# Driver2_TI.net
KiCad netlist of a schematic drawn in Altium Designer
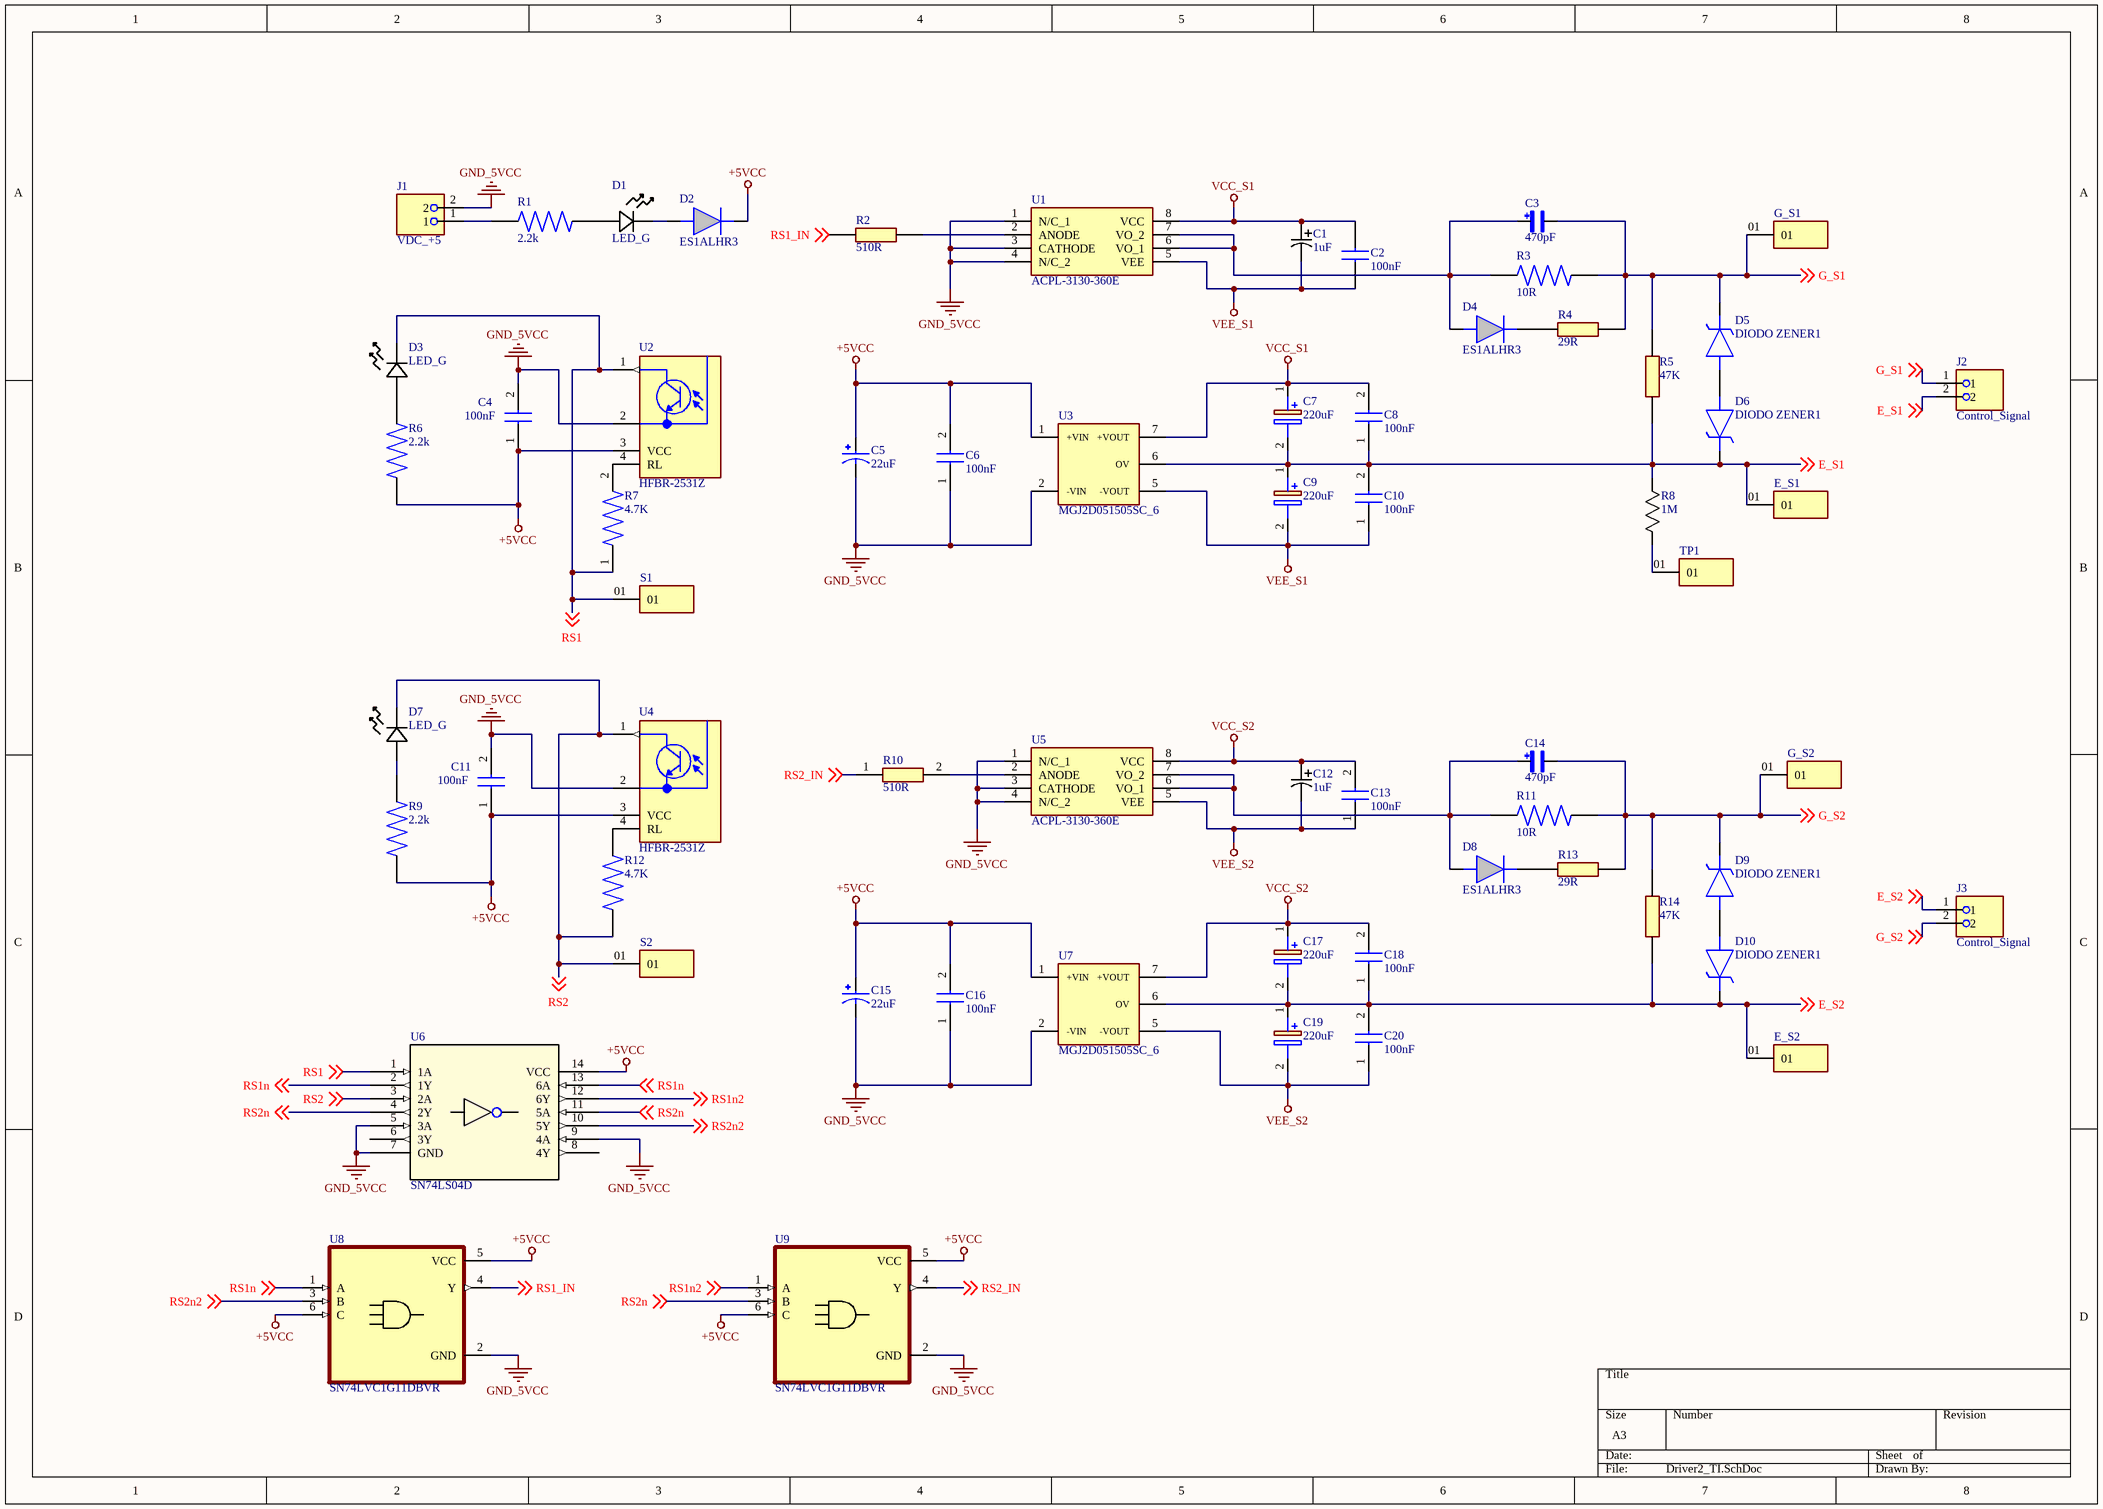
[diagram p0: Driver2_TI.SchDoc]

(export (version "E")
  (design (tool "Eeschema 10.0.6"))
  (components
    (comp (ref "C1")
      (value "1uF")
      (footprint "CAPAE430X550N")
      (description "Capacitor 1uF")
      (libsource (lib "Componentes") (part "UWX1H010MCL1GB"))
    )
    (comp (ref "C2")
      (value "100nF")
      (footprint "SamacSys:CAPC3216X94N")
      (description "Capacitor")
      (fields
        (field (name "MANUFACTURER_PART_NUMBER") "12063C104MAT2A")
        (field (name "MOUSER PART NUMBER") "581-12063C104MAT2A")
      )
      (libsource (lib "") (part "12063C104MAT2A_1"))
    )
    (comp (ref "C3")
      (value "470pF")
      (footprint "CAPC3216X94N")
      (description "Cap Ceramic 470pF 100V C0G 5% Pad SMD 1206 125Â°C T/R")
      (fields (field (name "MF") "KYOCERA AVX Components") (field (name "MP") "12061A471JAT2A"))
      (libsource (lib "Componentes") (part "MC1206N471J101CT"))
    )
    (comp (ref "C4")
      (value "100nF")
      (footprint "SamacSys:CAPC3216X94N")
      (description "Capacitor")
      (fields
        (field (name "MANUFACTURER_PART_NUMBER") "12063C104MAT2A")
        (field (name "MOUSER PART NUMBER") "581-12063C104MAT2A")
      )
      (libsource (lib "*") (part "12063C104MAT2A"))
    )
    (comp (ref "C5")
      (value "22uF")
      (footprint "CAP_EEE1HA220WP")
      (description "22ÂµF 50V Aluminum Electrolytic Capacitors Radial, Can - SMD 1000 Hrs @ 85Â°C")
      (fields (field (name "MF") "Panasonic") (field (name "MP") "EEE1HA220WP"))
      (libsource (lib "Componentes") (part "EEE1HA220WP"))
    )
    (comp (ref "C6")
      (value "100nF")
      (footprint "SamacSys:CAPC3216X94N")
      (description "Capacitor")
      (fields
        (field (name "MANUFACTURER_PART_NUMBER") "12063C104MAT2A")
        (field (name "MOUSER PART NUMBER") "581-12063C104MAT2A")
      )
      (libsource (lib "*") (part "12063C104MAT2A"))
    )
    (comp (ref "C7")
      (value "220uF")
      (footprint "SamacSys:CAPAE1050X1430N")
      (description "Capacitor Polarised")
      (fields
        (field (name "MANUFACTURER_PART_NUMBER") "MAL215097102E3")
        (field (name "MOUSER PART NUMBER") "594-MAL215097102E3")
      )
      (libsource (lib "*") (part "MAL215097102E3"))
    )
    (comp (ref "C8")
      (value "100nF")
      (footprint "SamacSys:CAPC3216X94N")
      (description "Capacitor")
      (fields
        (field (name "MANUFACTURER_PART_NUMBER") "12063C104MAT2A")
        (field (name "MOUSER PART NUMBER") "581-12063C104MAT2A")
      )
      (libsource (lib "*") (part "12063C104MAT2A"))
    )
    (comp (ref "C9")
      (value "220uF")
      (footprint "SamacSys:CAPAE1050X1430N")
      (description "Capacitor Polarised")
      (fields
        (field (name "MANUFACTURER_PART_NUMBER") "MAL215097102E3")
        (field (name "MOUSER PART NUMBER") "594-MAL215097102E3")
      )
      (libsource (lib "*") (part "MAL215097102E3"))
    )
    (comp (ref "C10")
      (value "100nF")
      (footprint "SamacSys:CAPC3216X94N")
      (description "Capacitor")
      (fields
        (field (name "MANUFACTURER_PART_NUMBER") "12063C104MAT2A")
        (field (name "MOUSER PART NUMBER") "581-12063C104MAT2A")
      )
      (libsource (lib "*") (part "12063C104MAT2A"))
    )
    (comp (ref "C11")
      (value "100nF")
      (footprint "SamacSys:CAPC3216X94N")
      (description "Capacitor")
      (fields
        (field (name "MANUFACTURER_PART_NUMBER") "12063C104MAT2A")
        (field (name "MOUSER PART NUMBER") "581-12063C104MAT2A")
      )
      (libsource (lib "*") (part "12063C104MAT2A"))
    )
    (comp (ref "C12")
      (value "1uF")
      (footprint "CAPAE430X550N")
      (description "Capacitor 1uF")
      (libsource (lib "Componentes") (part "UWX1H010MCL1GB"))
    )
    (comp (ref "C13")
      (value "100nF")
      (footprint "SamacSys:CAPC3216X94N")
      (description "Capacitor")
      (fields
        (field (name "MANUFACTURER_PART_NUMBER") "12063C104MAT2A")
        (field (name "MOUSER PART NUMBER") "581-12063C104MAT2A")
      )
      (libsource (lib "*") (part "12063C104MAT2A"))
    )
    (comp (ref "C14")
      (value "470pF")
      (footprint "CAPC3216X94N")
      (description "Cap Ceramic 470pF 100V C0G 5% Pad SMD 1206 125Â°C T/R")
      (fields (field (name "MF") "KYOCERA AVX Components") (field (name "MP") "12061A471JAT2A"))
      (libsource (lib "Componentes") (part "MC1206N471J101CT"))
    )
    (comp (ref "C15")
      (value "22uF")
      (footprint "CAP_EEE1HA220WP")
      (description "22ÂµF 50V Aluminum Electrolytic Capacitors Radial, Can - SMD 1000 Hrs @ 85Â°C")
      (fields (field (name "MF") "Panasonic") (field (name "MP") "EEE1HA220WP"))
      (libsource (lib "Componentes") (part "EEE1HA220WP"))
    )
    (comp (ref "C16")
      (value "100nF")
      (footprint "SamacSys:CAPC3216X94N")
      (description "Capacitor")
      (fields
        (field (name "MANUFACTURER_PART_NUMBER") "12063C104MAT2A")
        (field (name "MOUSER PART NUMBER") "581-12063C104MAT2A")
      )
      (libsource (lib "*") (part "12063C104MAT2A"))
    )
    (comp (ref "C17")
      (value "220uF")
      (footprint "SamacSys:CAPAE1050X1430N")
      (description "Capacitor Polarised")
      (fields
        (field (name "MANUFACTURER_PART_NUMBER") "MAL215097102E3")
        (field (name "MOUSER PART NUMBER") "594-MAL215097102E3")
      )
      (libsource (lib "*") (part "MAL215097102E3"))
    )
    (comp (ref "C18")
      (value "100nF")
      (footprint "SamacSys:CAPC3216X94N")
      (description "Capacitor")
      (fields
        (field (name "MANUFACTURER_PART_NUMBER") "12063C104MAT2A")
        (field (name "MOUSER PART NUMBER") "581-12063C104MAT2A")
      )
      (libsource (lib "*") (part "12063C104MAT2A"))
    )
    (comp (ref "C19")
      (value "220uF")
      (footprint "SamacSys:CAPAE1050X1430N")
      (description "Capacitor Polarised")
      (fields
        (field (name "MANUFACTURER_PART_NUMBER") "MAL215097102E3")
        (field (name "MOUSER PART NUMBER") "594-MAL215097102E3")
      )
      (libsource (lib "*") (part "MAL215097102E3"))
    )
    (comp (ref "C20")
      (value "100nF")
      (footprint "SamacSys:CAPC3216X94N")
      (description "Capacitor")
      (fields
        (field (name "MANUFACTURER_PART_NUMBER") "12063C104MAT2A")
        (field (name "MOUSER PART NUMBER") "581-12063C104MAT2A")
      )
      (libsource (lib "*") (part "12063C104MAT2A"))
    )
    (comp (ref "D1")
      (value "LED_G")
      (footprint "LED_KP-2012_KNB")
      (description "KP-2012SGC")
      (fields (field (name "COPYRIGHT") "Copyright (C) 2025 Ultra Librarian. All rights reserved."))
      (libsource (lib "Componentes") (part "KP-2012SGC"))
    )
    (comp (ref "D2")
      (value "ES1ALHR3")
      (footprint "DIOM4427X25M")
      (description "Rectifiers 1A, 50V, SUPER FAST SM RECTIFIER")
      (fields (field (name "MOUSER PART NUMBER") "821-ES1ALHR3"))
      (libsource (lib "Componentes") (part "ES1ALHR3_1"))
    )
    (comp (ref "D3")
      (value "LED_G")
      (footprint "LED_KP-2012_KNB")
      (description "KP-2012SGC")
      (fields (field (name "COPYRIGHT") "Copyright (C) 2025 Ultra Librarian. All rights reserved."))
      (libsource (lib "Componentes") (part "KP-2012SGC"))
    )
    (comp (ref "D4")
      (value "ES1ALHR3")
      (footprint "DIOM4427X25M")
      (description "Rectifiers 1A, 50V, SUPER FAST SM RECTIFIER")
      (fields (field (name "MOUSER PART NUMBER") "821-ES1ALHR3"))
      (libsource (lib "Componentes") (part "ES1ALHR3_1"))
    )
    (comp (ref "D5")
      (value "DIODO ZENER1")
      (footprint "SamacSys:DIOM5436X247N")
      (description "Zener Diode")
      (fields
        (field (name "MANUFACTURER_PART_NUMBER") "1SMB5931BT3G")
        (field (name "MOUSER PART NUMBER") "863-1SMB5931BT3G")
      )
      (libsource (lib "*") (part "1SMB5931BT3G"))
    )
    (comp (ref "D6")
      (value "DIODO ZENER1")
      (footprint "SamacSys:DIOM5436X247N")
      (description "Zener Diode")
      (fields
        (field (name "MANUFACTURER_PART_NUMBER") "1SMB5931BT3G")
        (field (name "MOUSER PART NUMBER") "863-1SMB5931BT3G")
      )
      (libsource (lib "*") (part "1SMB5931BT3G"))
    )
    (comp (ref "D7")
      (value "LED_G")
      (footprint "LED_KP-2012_KNB")
      (description "KP-2012SGC")
      (fields (field (name "COPYRIGHT") "Copyright (C) 2025 Ultra Librarian. All rights reserved."))
      (libsource (lib "Componentes") (part "KP-2012SGC"))
    )
    (comp (ref "D8")
      (value "ES1ALHR3")
      (footprint "DIOM4427X25M")
      (description "Rectifiers 1A, 50V, SUPER FAST SM RECTIFIER")
      (fields (field (name "MOUSER PART NUMBER") "821-ES1ALHR3"))
      (libsource (lib "Componentes") (part "ES1ALHR3_1"))
    )
    (comp (ref "D9")
      (value "DIODO ZENER1")
      (footprint "SamacSys:DIOM5436X247N")
      (description "Zener Diode")
      (fields
        (field (name "MANUFACTURER_PART_NUMBER") "1SMB5931BT3G")
        (field (name "MOUSER PART NUMBER") "863-1SMB5931BT3G")
      )
      (libsource (lib "*") (part "1SMB5931BT3G"))
    )
    (comp (ref "D10")
      (value "DIODO ZENER1")
      (footprint "SamacSys:DIOM5436X247N")
      (description "Zener Diode")
      (fields
        (field (name "MANUFACTURER_PART_NUMBER") "1SMB5931BT3G")
        (field (name "MOUSER PART NUMBER") "863-1SMB5931BT3G")
      )
      (libsource (lib "*") (part "1SMB5931BT3G"))
    )
    (comp (ref "E_S1")
      (value "MTMM-101-X-X-S-X")
      (footprint "SAMTEC_MTMM-101-X-X-S-X")
      (description "Connector Header Through Hole 1 position")
      (fields (field (name "MF") "Samtec") (field (name "MP") "MTMM-101-05-G-S-225"))
      (libsource (lib "Componentes") (part "MTMM-101-X-X-S-X"))
    )
    (comp (ref "E_S2")
      (value "MTMM-101-X-X-S-X")
      (footprint "SAMTEC_MTMM-101-X-X-S-X")
      (description "Connector Header Through Hole 1 position")
      (fields (field (name "MF") "Samtec") (field (name "MP") "MTMM-101-05-G-S-225"))
      (libsource (lib "Componentes") (part "MTMM-101-X-X-S-X"))
    )
    (comp (ref "G_S1")
      (value "MTMM-101-X-X-S-X")
      (footprint "SAMTEC_MTMM-101-X-X-S-X")
      (description "Connector Header Through Hole 1 position")
      (fields (field (name "MF") "Samtec") (field (name "MP") "MTMM-101-05-G-S-225"))
      (libsource (lib "Componentes") (part "MTMM-101-X-X-S-X"))
    )
    (comp (ref "G_S2")
      (value "MTMM-101-X-X-S-X")
      (footprint "SAMTEC_MTMM-101-X-X-S-X")
      (description "Connector Header Through Hole 1 position")
      (fields (field (name "MF") "Samtec") (field (name "MP") "MTMM-101-05-G-S-225"))
      (libsource (lib "Componentes") (part "MTMM-101-X-X-S-X"))
    )
    (comp (ref "J1")
      (value "VDC_+5")
      (footprint "PHOENIX_1725656")
      (description "Conn PC Terminal Block 2 POS 2.54mm Solder ST Thru-Hole 6A Cardboard")
      (libsource (lib "") (part "1725656_1"))
    )
    (comp (ref "J2")
      (value "Control_Signal")
      (footprint "PHOENIX_1725656")
      (description "Conn PC Terminal Block 2 POS 2.54mm Solder ST Thru-Hole 6A Cardboard")
      (libsource (lib "Componentes") (part "1725656"))
    )
    (comp (ref "J3")
      (value "Control_Signal")
      (footprint "PHOENIX_1725656")
      (description "Conn PC Terminal Block 2 POS 2.54mm Solder ST Thru-Hole 6A Cardboard")
      (libsource (lib "Componentes") (part "1725656"))
    )
    (comp (ref "R1")
      (value "2.2k")
      (footprint "RES_ERJS08F2201V")
      (description "ERJS08F2201V")
      (libsource (lib "Componentes") (part "ERJS08F2201V"))
    )
    (comp (ref "R2")
      (value "510R")
      (footprint "SamacSys:RESC3216X60N")
      (description "Resistor")
      (fields
        (field (name "MANUFACTURER_PART_NUMBER") "CRCW1206510RFKEA")
        (field (name "MOUSER PART NUMBER") "71-CRCW1206-510-E3")
      )
      (libsource (lib "*") (part "CRCW1206510RFKEA"))
    )
    (comp (ref "R3")
      (value "10R")
      (footprint "RESC6331X70N")
      (fields (field (name "MF") "Vishay") (field (name "MP") "CRCW251210R0FKEGHP"))
      (libsource (lib "Componentes") (part "CRCW251210R0FKEGHP"))
    )
    (comp (ref "R4")
      (value "29R")
      (footprint "SamacSys:ERJ8ENF1000V")
      (description "Resistor")
      (fields
        (field (name "MANUFACTURER_PART_NUMBER") "ERJ-8ENF30R0V")
        (field (name "MOUSER PART NUMBER") "667-ERJ-8ENF30R0V")
      )
      (libsource (lib "*") (part "ERJ-8ENF30R0V"))
    )
    (comp (ref "R5")
      (value "47K")
      (footprint "SamacSys:RESC3216X60N")
      (description "Resistor")
      (fields
        (field (name "MANUFACTURER_PART_NUMBER") "CRCW120647K0FKEA")
        (field (name "MOUSER PART NUMBER") "71-CRCW1206-47K-E3")
      )
      (libsource (lib "*") (part "CRCW120647K0FKEA"))
    )
    (comp (ref "R6")
      (value "2.2k")
      (footprint "RES_ERJS08F2201V")
      (description "Resistor Film ERJS08F2201V")
      (fields (field (name "MP") "ERJS08F2201V"))
      (libsource (lib "Componentes") (part "ERJS08F2201V"))
    )
    (comp (ref "R7")
      (value "4.7K")
      (footprint "RESC3116X65N")
      (description "RES, SMD, 4.7K ohm, 0.5W, 1%, 1206, TCR100 ¦ Bourns CRS1206-FX-4701ELF")
      (fields (field (name "MF") "Bourns") (field (name "MP") "CRS1206-FX-4701ELF"))
      (libsource (lib "Componentes") (part "CRS1206-FX-4701ELF"))
    )
    (comp (ref "R8")
      (value "1M")
      (footprint "RESC6331X70N")
      (description "Resistencia SMD de Tipo Chip, 1 Mohm, ± 1%, 1 W, 2512 [Métrica 6432], Película Gruesa")
      (libsource (lib "Componentes") (part "HV733ATTE1004F"))
    )
    (comp (ref "R9")
      (value "2.2k")
      (footprint "RES_ERJS08F2201V")
      (description "Resistor Film ERJS08F2201V")
      (fields (field (name "MP") "ERJS08F2201V"))
      (libsource (lib "Componentes") (part "ERJS08F2201V"))
    )
    (comp (ref "R10")
      (value "510R")
      (footprint "SamacSys:RESC3216X60N")
      (description "Resistor")
      (fields
        (field (name "MANUFACTURER_PART_NUMBER") "CRCW1206510RFKEA")
        (field (name "MOUSER PART NUMBER") "71-CRCW1206-510-E3")
      )
      (libsource (lib "") (part "CRCW1206510RFKEA_1"))
    )
    (comp (ref "R11")
      (value "10R")
      (footprint "RESC6331X70N")
      (fields (field (name "MF") "Vishay") (field (name "MP") "CRCW251210R0FKEGHP"))
      (libsource (lib "Componentes") (part "CRCW251210R0FKEGHP"))
    )
    (comp (ref "R12")
      (value "4.7K")
      (footprint "RESC3116X65N")
      (description "RES, SMD, 4.7K ohm, 0.5W, 1%, 1206, TCR100 ¦ Bourns CRS1206-FX-4701ELF")
      (fields (field (name "MF") "Bourns") (field (name "MP") "CRS1206-FX-4701ELF"))
      (libsource (lib "") (part "CRS1206-FX-4701ELF_1"))
    )
    (comp (ref "R13")
      (value "29R")
      (footprint "SamacSys:ERJ8ENF1000V")
      (description "Resistor")
      (fields
        (field (name "MANUFACTURER_PART_NUMBER") "ERJ-8ENF30R0V")
        (field (name "MOUSER PART NUMBER") "667-ERJ-8ENF30R0V")
      )
      (libsource (lib "*") (part "ERJ-8ENF30R0V"))
    )
    (comp (ref "R14")
      (value "47K")
      (footprint "SamacSys:RESC3216X60N")
      (description "Resistor")
      (fields
        (field (name "MANUFACTURER_PART_NUMBER") "CRCW120647K0FKEA")
        (field (name "MOUSER PART NUMBER") "71-CRCW1206-47K-E3")
      )
      (libsource (lib "*") (part "CRCW120647K0FKEA"))
    )
    (comp (ref "S1")
      (value "MTMM-101-X-X-S-X")
      (footprint "SAMTEC_MTMM-101-X-X-S-X")
      (description "Connector Header Through Hole 1 position")
      (fields (field (name "MF") "Samtec") (field (name "MP") "MTMM-101-05-G-S-225"))
      (libsource (lib "Componentes") (part "MTMM-101-X-X-S-X"))
    )
    (comp (ref "S2")
      (value "MTMM-101-X-X-S-X")
      (footprint "SAMTEC_MTMM-101-X-X-S-X")
      (description "Connector Header Through Hole 1 position")
      (fields (field (name "MF") "Samtec") (field (name "MP") "MTMM-101-05-G-S-225"))
      (libsource (lib "Componentes") (part "MTMM-101-X-X-S-X"))
    )
    (comp (ref "TP1")
      (value "MTMM-101-X-X-S-X")
      (footprint "SAMTEC_MTMM-101-X-X-S-X")
      (description "Connector Header Through Hole 1 position")
      (fields (field (name "MF") "Samtec") (field (name "MP") "MTMM-101-05-G-S-225"))
      (libsource (lib "Componentes") (part "MTMM-101-X-X-S-X"))
    )
    (comp (ref "U1")
      (value "ACPL-3130-360E")
      (footprint "DIP794W53P254L959H508Q8N")
      (description "Integrated Circuit")
      (fields (field (name "MOUSER PART NUMBER") "630-ACPL-3130-360E"))
      (libsource (lib "Componentes") (part "ACPL-3130-360E"))
    )
    (comp (ref "U2")
      (value "HFBR-2531Z")
      (footprint "XDCR_HFBR-2531Z")
      (description "Fiber Optic Receiver - 5MBd - 7V 10 mA")
      (fields (field (name "MF") "Broadcom Limited"))
      (libsource (lib "Componentes") (part "HFBR-2531Z"))
    )
    (comp (ref "U3")
      (value "MGJ2D051505SC_6")
      (footprint "Componentes:MGJ2D051505SC")
      (description "Undefined or Miscellaneous")
      (fields
        (field (name "MANUFACTURER_PART_NUMBER") "MGJ2D051505SC")
        (field (name "MOUSER PART NUMBER") "580-MGJ2D051505SC")
      )
      (libsource (lib "*") (part "MGJ2D051505SC"))
    )
    (comp (ref "U4")
      (value "HFBR-2531Z")
      (footprint "XDCR_HFBR-2531Z")
      (description "Fiber Optic Receiver - 5MBd - 7V 10 mA")
      (fields (field (name "MF") "Broadcom Limited"))
      (libsource (lib "Componentes") (part "HFBR-2531Z"))
    )
    (comp (ref "U5")
      (value "ACPL-3130-360E")
      (footprint "DIP794W53P254L959H508Q8N")
      (description "Integrated Circuit")
      (fields (field (name "MOUSER PART NUMBER") "630-ACPL-3130-360E"))
      (libsource (lib "Componentes") (part "ACPL-3130-360E"))
    )
    (comp (ref "U6")
      (value "SN74LS04D")
      (footprint "D14")
      (description "Integrated Circuit")
      (libsource (lib "Componentes") (part "SN74LS04D"))
    )
    (comp (ref "U7")
      (value "MGJ2D051505SC_6")
      (footprint "Componentes:MGJ2D051505SC")
      (description "Undefined or Miscellaneous")
      (fields
        (field (name "MANUFACTURER_PART_NUMBER") "MGJ2D051505SC")
        (field (name "MOUSER PART NUMBER") "580-MGJ2D051505SC")
      )
      (libsource (lib "*") (part "MGJ2D051505SC"))
    )
    (comp (ref "U8")
      (value "SN74LVC1G11DBVR")
      (footprint "SOT95P280X145-6N")
      (description "1-ch, 3-input 1.65-V to 5.5-V 32 mA drive strength AND gate")
      (fields (field (name "MF") "Texas Instruments"))
      (libsource (lib "Componentes") (part "SN74LVC1G11DBVR"))
    )
    (comp (ref "U9")
      (value "SN74LVC1G11DBVR")
      (footprint "SOT95P280X145-6N")
      (description "1-ch, 3-input 1.65-V to 5.5-V 32 mA drive strength AND gate")
      (fields (field (name "MF") "Texas Instruments"))
      (libsource (lib "Componentes") (part "SN74LVC1G11DBVR"))
    )
  )
  (nets
    (net (code "1") (name "+5VCC") (class "Default")
      (node (ref "C11") (pin "1") (pinfunction "C1_1") (pintype "passive"))
      (node (ref "C15") (pin "1") (pinfunction "1_1") (pintype "passive"))
      (node (ref "C16") (pin "2") (pinfunction "C2_2") (pintype "passive"))
      (node (ref "C4") (pin "1") (pinfunction "C1_1") (pintype "passive"))
      (node (ref "C5") (pin "1") (pinfunction "1_1") (pintype "passive"))
      (node (ref "C6") (pin "2") (pinfunction "C2_2") (pintype "passive"))
      (node (ref "D2") (pin "1") (pinfunction "K_1") (pintype "passive"))
      (node (ref "R6") (pin "1") (pinfunction "1_1") (pintype "passive"))
      (node (ref "R9") (pin "1") (pinfunction "1_1") (pintype "passive"))
      (node (ref "U2") (pin "3") (pinfunction "VCC_3") (pintype "power_in"))
      (node (ref "U3") (pin "1") (pinfunction "+VIN_1") (pintype "passive"))
      (node (ref "U4") (pin "3") (pinfunction "VCC_3") (pintype "power_in"))
      (node (ref "U6") (pin "14") (pinfunction "VCC_14") (pintype "power_in"))
      (node (ref "U7") (pin "1") (pinfunction "+VIN_1") (pintype "passive"))
      (node (ref "U8") (pin "5") (pinfunction "VCC_5") (pintype "power_in"))
      (node (ref "U8") (pin "6") (pinfunction "C_6") (pintype "input"))
      (node (ref "U9") (pin "5") (pinfunction "VCC_5") (pintype "power_in"))
      (node (ref "U9") (pin "6") (pinfunction "C_6") (pintype "input"))
    )
    (net (code "2") (name "E_S1") (class "Default")
      (node (ref "C10") (pin "2") (pinfunction "C2_2") (pintype "passive"))
      (node (ref "C7") (pin "2") (pinfunction "-_2") (pintype "passive"))
      (node (ref "C8") (pin "1") (pinfunction "C1_1") (pintype "passive"))
      (node (ref "C9") (pin "1") (pinfunction "+_1") (pintype "passive"))
      (node (ref "D6") (pin "1") (pinfunction "K_1") (pintype "passive"))
      (node (ref "E_S1") (pin "01") (pinfunction "01_01") (pintype "passive"))
      (node (ref "J2") (pin "2") (pinfunction "2_2") (pintype "passive"))
      (node (ref "R5") (pin "1") (pinfunction "1_1") (pintype "passive"))
      (node (ref "R8") (pin "2") (pinfunction "2_2") (pintype "passive"))
      (node (ref "U3") (pin "6") (pinfunction "OV_6") (pintype "passive"))
    )
    (net (code "3") (name "E_S2") (class "Default")
      (node (ref "C17") (pin "2") (pinfunction "-_2") (pintype "passive"))
      (node (ref "C18") (pin "1") (pinfunction "C1_1") (pintype "passive"))
      (node (ref "C19") (pin "1") (pinfunction "+_1") (pintype "passive"))
      (node (ref "C20") (pin "2") (pinfunction "C2_2") (pintype "passive"))
      (node (ref "D10") (pin "1") (pinfunction "K_1") (pintype "passive"))
      (node (ref "E_S2") (pin "01") (pinfunction "01_01") (pintype "passive"))
      (node (ref "J3") (pin "1") (pinfunction "1_1") (pintype "passive"))
      (node (ref "R14") (pin "1") (pinfunction "1_1") (pintype "passive"))
      (node (ref "U7") (pin "6") (pinfunction "OV_6") (pintype "passive"))
    )
    (net (code "4") (name "GND_5VCC") (class "Default")
      (node (ref "C11") (pin "2") (pinfunction "C2_2") (pintype "passive"))
      (node (ref "C15") (pin "2") (pinfunction "2_2") (pintype "passive"))
      (node (ref "C16") (pin "1") (pinfunction "C1_1") (pintype "passive"))
      (node (ref "C4") (pin "2") (pinfunction "C2_2") (pintype "passive"))
      (node (ref "C5") (pin "2") (pinfunction "2_2") (pintype "passive"))
      (node (ref "C6") (pin "1") (pinfunction "C1_1") (pintype "passive"))
      (node (ref "J1") (pin "2") (pinfunction "2_2") (pintype "passive"))
      (node (ref "U1") (pin "1") (pinfunction "N/C_1_1") (pintype "passive"))
      (node (ref "U1") (pin "3") (pinfunction "CATHODE_3") (pintype "passive"))
      (node (ref "U1") (pin "4") (pinfunction "N/C_2_4") (pintype "passive"))
      (node (ref "U2") (pin "2") (pinfunction "GROUND_2") (pintype "power_in"))
      (node (ref "U3") (pin "2") (pinfunction "-VIN_2") (pintype "passive"))
      (node (ref "U4") (pin "2") (pinfunction "GROUND_2") (pintype "power_in"))
      (node (ref "U5") (pin "1") (pinfunction "N/C_1_1") (pintype "passive"))
      (node (ref "U5") (pin "3") (pinfunction "CATHODE_3") (pintype "passive"))
      (node (ref "U5") (pin "4") (pinfunction "N/C_2_4") (pintype "passive"))
      (node (ref "U6") (pin "5") (pinfunction "3A_5") (pintype "input"))
      (node (ref "U6") (pin "7") (pinfunction "GND_7") (pintype "power_in"))
      (node (ref "U6") (pin "9") (pinfunction "4A_9") (pintype "input"))
      (node (ref "U7") (pin "2") (pinfunction "-VIN_2") (pintype "passive"))
      (node (ref "U8") (pin "2") (pinfunction "GND_2") (pintype "power_in"))
      (node (ref "U9") (pin "2") (pinfunction "GND_2") (pintype "power_in"))
    )
    (net (code "5") (name "G_S1") (class "Default")
      (node (ref "C3") (pin "2") (pinfunction "2_2") (pintype "passive"))
      (node (ref "D5") (pin "1") (pinfunction "K_1") (pintype "passive"))
      (node (ref "G_S1") (pin "01") (pinfunction "01_01") (pintype "passive"))
      (node (ref "J2") (pin "1") (pinfunction "1_1") (pintype "passive"))
      (node (ref "R3") (pin "2") (pinfunction "2_2") (pintype "passive"))
      (node (ref "R4") (pin "2") (pinfunction "2_2") (pintype "passive"))
      (node (ref "R5") (pin "2") (pinfunction "2_2") (pintype "passive"))
    )
    (net (code "6") (name "G_S2") (class "Default")
      (node (ref "C14") (pin "2") (pinfunction "2_2") (pintype "passive"))
      (node (ref "D9") (pin "1") (pinfunction "K_1") (pintype "passive"))
      (node (ref "G_S2") (pin "01") (pinfunction "01_01") (pintype "passive"))
      (node (ref "J3") (pin "2") (pinfunction "2_2") (pintype "passive"))
      (node (ref "R11") (pin "2") (pinfunction "2_2") (pintype "passive"))
      (node (ref "R13") (pin "2") (pinfunction "2_2") (pintype "passive"))
      (node (ref "R14") (pin "2") (pinfunction "2_2") (pintype "passive"))
    )
    (net (code "7") (name "Net-(D1-ANODE)") (class "Default")
      (node (ref "D1") (pin "2") (pinfunction "ANODE_2") (pintype "passive"))
      (node (ref "R1") (pin "2") (pinfunction "2_2") (pintype "passive"))
    )
    (net (code "8") (name "Net-(D1-CATHODE)") (class "Default")
      (node (ref "D1") (pin "1") (pinfunction "CATHODE_1") (pintype "passive"))
      (node (ref "D2") (pin "2") (pinfunction "A_2") (pintype "passive"))
    )
    (net (code "9") (name "Net-(D3-ANODE)") (class "Default")
      (node (ref "D3") (pin "2") (pinfunction "ANODE_2") (pintype "passive"))
      (node (ref "R6") (pin "2") (pinfunction "2_2") (pintype "passive"))
    )
    (net (code "10") (name "Net-(D4-A)") (class "Default")
      (node (ref "C3") (pin "1") (pinfunction "1_1") (pintype "passive"))
      (node (ref "D4") (pin "2") (pinfunction "A_2") (pintype "passive"))
      (node (ref "R3") (pin "1") (pinfunction "1_1") (pintype "passive"))
      (node (ref "U1") (pin "6") (pinfunction "VO_1_6") (pintype "passive"))
      (node (ref "U1") (pin "7") (pinfunction "VO_2_7") (pintype "passive"))
    )
    (net (code "11") (name "Net-(D4-K)") (class "Default")
      (node (ref "D4") (pin "1") (pinfunction "K_1") (pintype "passive"))
      (node (ref "R4") (pin "1") (pinfunction "1_1") (pintype "passive"))
    )
    (net (code "12") (name "Net-(D5-A)") (class "Default")
      (node (ref "D5") (pin "2") (pinfunction "A_2") (pintype "passive"))
      (node (ref "D6") (pin "2") (pinfunction "A_2") (pintype "passive"))
    )
    (net (code "13") (name "Net-(D7-ANODE)") (class "Default")
      (node (ref "D7") (pin "2") (pinfunction "ANODE_2") (pintype "passive"))
      (node (ref "R9") (pin "2") (pinfunction "2_2") (pintype "passive"))
    )
    (net (code "14") (name "Net-(D8-A)") (class "Default")
      (node (ref "C14") (pin "1") (pinfunction "1_1") (pintype "passive"))
      (node (ref "D8") (pin "2") (pinfunction "A_2") (pintype "passive"))
      (node (ref "R11") (pin "1") (pinfunction "1_1") (pintype "passive"))
      (node (ref "U5") (pin "6") (pinfunction "VO_1_6") (pintype "passive"))
      (node (ref "U5") (pin "7") (pinfunction "VO_2_7") (pintype "passive"))
    )
    (net (code "15") (name "Net-(D8-K)") (class "Default")
      (node (ref "D8") (pin "1") (pinfunction "K_1") (pintype "passive"))
      (node (ref "R13") (pin "1") (pinfunction "1_1") (pintype "passive"))
    )
    (net (code "16") (name "Net-(D10-A)") (class "Default")
      (node (ref "D10") (pin "2") (pinfunction "A_2") (pintype "passive"))
      (node (ref "D9") (pin "2") (pinfunction "A_2") (pintype "passive"))
    )
    (net (code "17") (name "Net-(J1-Pad1)") (class "Default")
      (node (ref "J1") (pin "1") (pinfunction "1_1") (pintype "passive"))
      (node (ref "R1") (pin "1") (pinfunction "1_1") (pintype "passive"))
    )
    (net (code "18") (name "Net-(R8-Pad1)") (class "Default")
      (node (ref "R8") (pin "1") (pinfunction "1_1") (pintype "passive"))
      (node (ref "TP1") (pin "01") (pinfunction "01_01") (pintype "passive"))
    )
    (net (code "19") (name "Net-(U1-ANODE)") (class "Default")
      (node (ref "R2") (pin "2") (pinfunction "2_2") (pintype "passive"))
      (node (ref "U1") (pin "2") (pinfunction "ANODE_2") (pintype "passive"))
    )
    (net (code "20") (name "Net-(U2-RL)") (class "Default")
      (node (ref "R7") (pin "2") (pinfunction "2_2") (pintype "passive"))
      (node (ref "U2") (pin "4") (pinfunction "RL_4") (pintype "passive"))
    )
    (net (code "21") (name "Net-(U4-RL)") (class "Default")
      (node (ref "R12") (pin "2") (pinfunction "2_2") (pintype "passive"))
      (node (ref "U4") (pin "4") (pinfunction "RL_4") (pintype "passive"))
    )
    (net (code "22") (name "Net-(U5-ANODE)") (class "Default")
      (node (ref "R10") (pin "2") (pinfunction "2_2") (pintype "passive"))
      (node (ref "U5") (pin "2") (pinfunction "ANODE_2") (pintype "passive"))
    )
    (net (code "23") (name "RS1") (class "Default")
      (node (ref "D3") (pin "1") (pinfunction "CATHODE_1") (pintype "passive"))
      (node (ref "R7") (pin "1") (pinfunction "1_1") (pintype "passive"))
      (node (ref "S1") (pin "01") (pinfunction "01_01") (pintype "passive"))
      (node (ref "U2") (pin "1") (pinfunction "VO_1") (pintype "output"))
      (node (ref "U6") (pin "1") (pinfunction "1A_1") (pintype "input"))
    )
    (net (code "24") (name "RS1_IN") (class "Default")
      (node (ref "R2") (pin "1") (pinfunction "1_1") (pintype "passive"))
      (node (ref "U8") (pin "4") (pinfunction "Y_4") (pintype "output"))
    )
    (net (code "25") (name "RS1n") (class "Default")
      (node (ref "U6") (pin "13") (pinfunction "6A_13") (pintype "input"))
      (node (ref "U6") (pin "2") (pinfunction "1Y_2") (pintype "output"))
      (node (ref "U8") (pin "1") (pinfunction "A_1") (pintype "input"))
    )
    (net (code "26") (name "RS1n2") (class "Default")
      (node (ref "U6") (pin "12") (pinfunction "6Y_12") (pintype "output"))
      (node (ref "U9") (pin "1") (pinfunction "A_1") (pintype "input"))
    )
    (net (code "27") (name "RS2") (class "Default")
      (node (ref "D7") (pin "1") (pinfunction "CATHODE_1") (pintype "passive"))
      (node (ref "R12") (pin "1") (pinfunction "1_1") (pintype "passive"))
      (node (ref "S2") (pin "01") (pinfunction "01_01") (pintype "passive"))
      (node (ref "U4") (pin "1") (pinfunction "VO_1") (pintype "output"))
      (node (ref "U6") (pin "3") (pinfunction "2A_3") (pintype "input"))
    )
    (net (code "28") (name "RS2_IN") (class "Default")
      (node (ref "R10") (pin "1") (pinfunction "1_1") (pintype "passive"))
      (node (ref "U9") (pin "4") (pinfunction "Y_4") (pintype "output"))
    )
    (net (code "29") (name "RS2n") (class "Default")
      (node (ref "U6") (pin "11") (pinfunction "5A_11") (pintype "input"))
      (node (ref "U6") (pin "4") (pinfunction "2Y_4") (pintype "output"))
      (node (ref "U9") (pin "3") (pinfunction "B_3") (pintype "input"))
    )
    (net (code "30") (name "RS2n2") (class "Default")
      (node (ref "U6") (pin "10") (pinfunction "5Y_10") (pintype "output"))
      (node (ref "U8") (pin "3") (pinfunction "B_3") (pintype "input"))
    )
    (net (code "31") (name "VCC_S1") (class "Default")
      (node (ref "C1") (pin "1") (pinfunction "1_1") (pintype "passive"))
      (node (ref "C2") (pin "2") (pinfunction "C2_2") (pintype "passive"))
      (node (ref "C7") (pin "1") (pinfunction "+_1") (pintype "passive"))
      (node (ref "C8") (pin "2") (pinfunction "C2_2") (pintype "passive"))
      (node (ref "U1") (pin "8") (pinfunction "VCC_8") (pintype "passive"))
      (node (ref "U3") (pin "7") (pinfunction "+VOUT_7") (pintype "passive"))
    )
    (net (code "32") (name "VCC_S2") (class "Default")
      (node (ref "C12") (pin "1") (pinfunction "1_1") (pintype "passive"))
      (node (ref "C13") (pin "2") (pinfunction "C2_2") (pintype "passive"))
      (node (ref "C17") (pin "1") (pinfunction "+_1") (pintype "passive"))
      (node (ref "C18") (pin "2") (pinfunction "C2_2") (pintype "passive"))
      (node (ref "U5") (pin "8") (pinfunction "VCC_8") (pintype "passive"))
      (node (ref "U7") (pin "7") (pinfunction "+VOUT_7") (pintype "passive"))
    )
    (net (code "33") (name "VEE_S1") (class "Default")
      (node (ref "C1") (pin "2") (pinfunction "2_2") (pintype "passive"))
      (node (ref "C10") (pin "1") (pinfunction "C1_1") (pintype "passive"))
      (node (ref "C2") (pin "1") (pinfunction "C1_1") (pintype "passive"))
      (node (ref "C9") (pin "2") (pinfunction "-_2") (pintype "passive"))
      (node (ref "U1") (pin "5") (pinfunction "VEE_5") (pintype "passive"))
      (node (ref "U3") (pin "5") (pinfunction "-VOUT_5") (pintype "passive"))
    )
    (net (code "34") (name "VEE_S2") (class "Default")
      (node (ref "C12") (pin "2") (pinfunction "2_2") (pintype "passive"))
      (node (ref "C13") (pin "1") (pinfunction "C1_1") (pintype "passive"))
      (node (ref "C19") (pin "2") (pinfunction "-_2") (pintype "passive"))
      (node (ref "C20") (pin "1") (pinfunction "C1_1") (pintype "passive"))
      (node (ref "U5") (pin "5") (pinfunction "VEE_5") (pintype "passive"))
      (node (ref "U7") (pin "5") (pinfunction "-VOUT_5") (pintype "passive"))
    )
    (net (code "35") (name "unconnected-(U6-3Y-Pad6)") (class "Default")
      (node (ref "U6") (pin "6") (pinfunction "3Y_6") (pintype "output"))
    )
    (net (code "36") (name "unconnected-(U6-4Y-Pad8)") (class "Default")
      (node (ref "U6") (pin "8") (pinfunction "4Y_8") (pintype "output"))
    )
  )
)
